# Board_Schamatic04.net
KiCad netlist of a schematic drawn in EAGLE
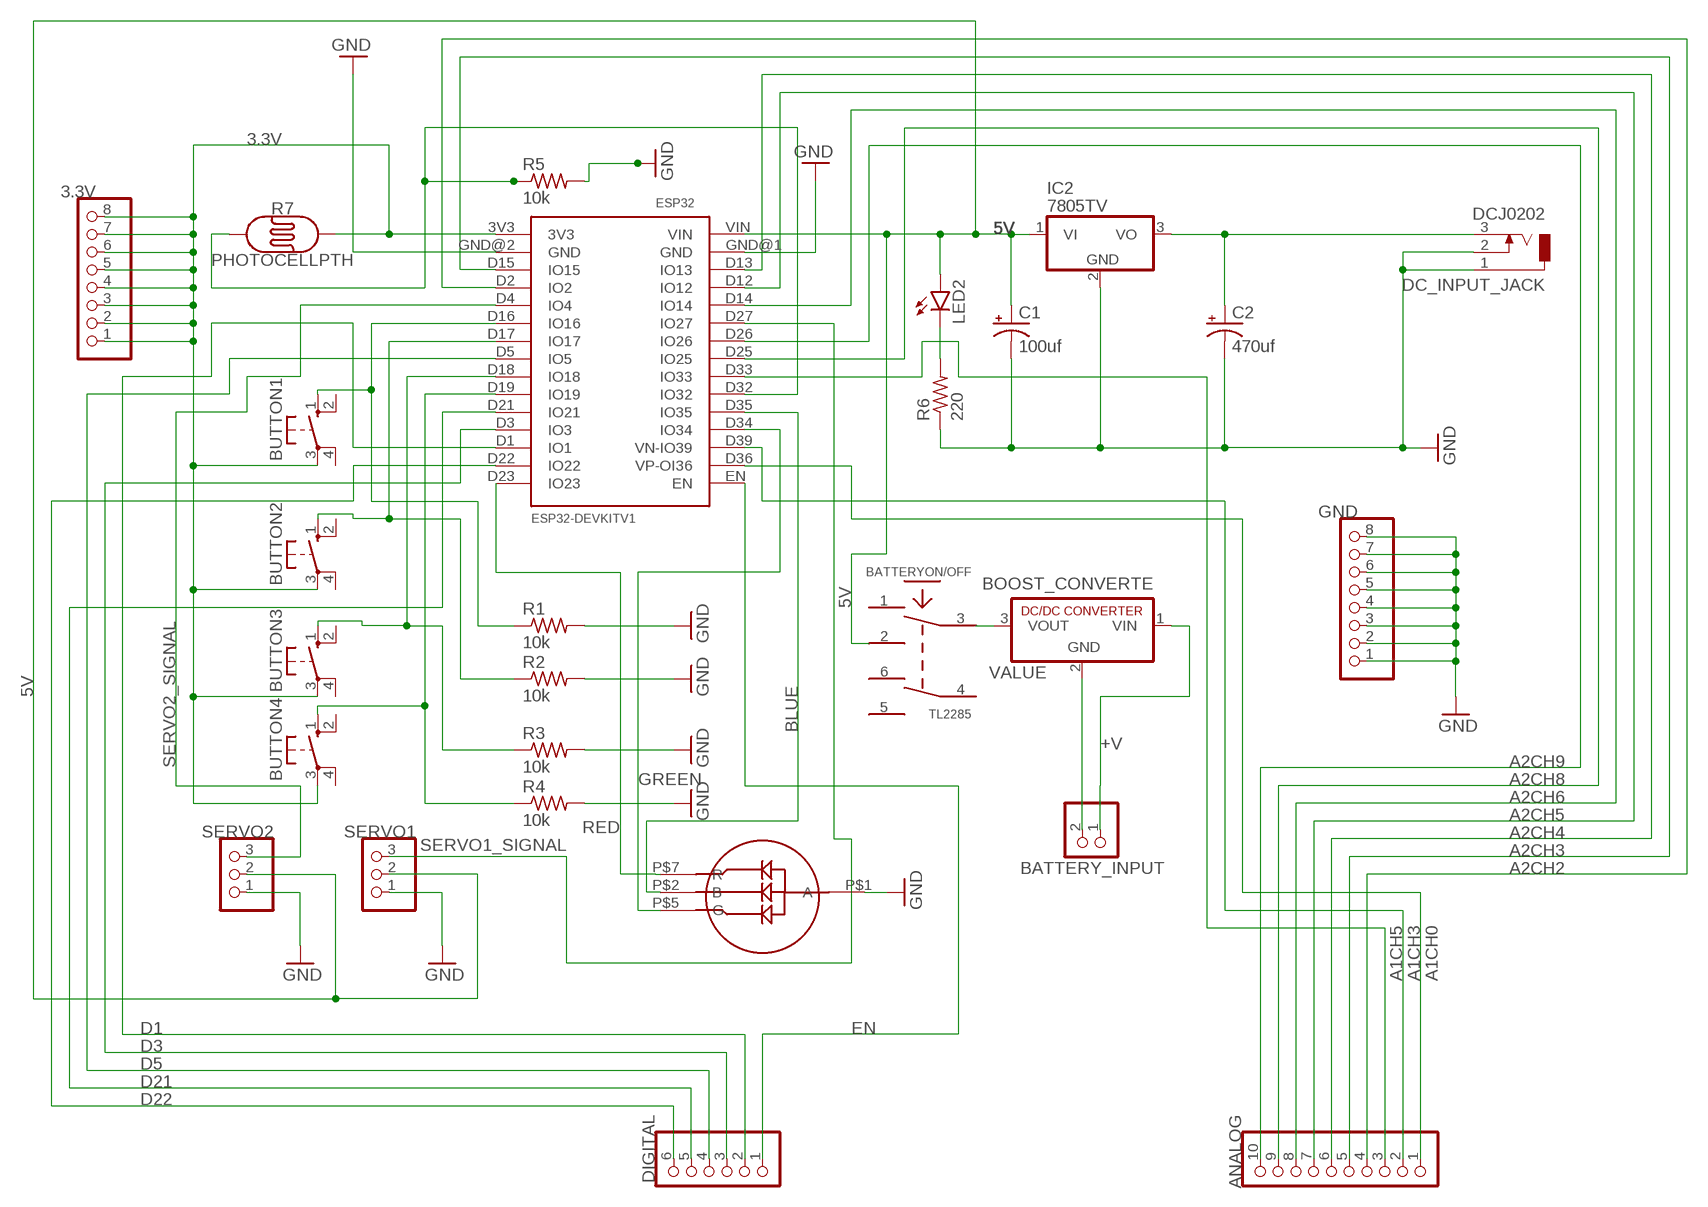
[diagram p0: schematic, sheet 1]

(export (version "E")
  (design (tool "Eeschema 10.0.6"))
  (components
    (comp (ref "3.3V")
      (value "PINHD-1X8")
      (footprint "eagle-import:1X08")
      (libsource (lib "eagle-import") (part "PINHD-1X8"))
    )
    (comp (ref "ANALOG")
      (value "PINHD-1X10")
      (footprint "eagle-import:1X10")
      (libsource (lib "eagle-import") (part "PINHD-1X10"))
    )
    (comp (ref "BATTERYON/OFF")
      (value "TL2285")
      (footprint "eagle-import:TL2285_PCB")
      (libsource (lib "eagle-import") (part "TL2285"))
    )
    (comp (ref "BATTERY_INPUT")
      (value "PINHD-1X2")
      (footprint "eagle-import:1X02")
      (libsource (lib "eagle-import") (part "PINHD-1X2"))
    )
    (comp (ref "BOOST_CONVERTE")
      (value "R-78C1.8-1.0")
      (footprint "eagle-import:SIP3")
      (libsource (lib "eagle-import") (part "R-78C-1.01.8"))
    )
    (comp (ref "BUTTON1")
      (value "10-XX")
      (footprint "eagle-import:B3F-10XX")
      (fields (field (name "MPN") "B3F-1000"))
      (libsource (lib "eagle-import") (part "10-XX"))
    )
    (comp (ref "BUTTON2")
      (value "10-XX")
      (footprint "eagle-import:B3F-10XX")
      (fields (field (name "MPN") "B3F-1000"))
      (libsource (lib "eagle-import") (part "10-XX"))
    )
    (comp (ref "BUTTON3")
      (value "10-XX")
      (footprint "eagle-import:B3F-10XX")
      (fields (field (name "MPN") "B3F-1000"))
      (libsource (lib "eagle-import") (part "10-XX"))
    )
    (comp (ref "BUTTON4")
      (value "10-XX")
      (footprint "eagle-import:B3F-10XX")
      (fields (field (name "MPN") "B3F-1000"))
      (libsource (lib "eagle-import") (part "10-XX"))
    )
    (comp (ref "C1")
      (value "100uf")
      (footprint "eagle-import:E2-5")
      (libsource (lib "eagle-import") (part "CPOL-USE2-5"))
    )
    (comp (ref "C2")
      (value "470uf")
      (footprint "eagle-import:E2-5")
      (libsource (lib "eagle-import") (part "CPOL-USE2-5"))
    )
    (comp (ref "DC_INPUT_JACK")
      (value "DCJ0202")
      (footprint "eagle-import:DCJ0202")
      (libsource (lib "eagle-import") (part "DCJ0202"))
    )
    (comp (ref "DIGITAL")
      (value "PINHD-1X6")
      (footprint "eagle-import:1X06")
      (libsource (lib "eagle-import") (part "PINHD-1X6"))
    )
    (comp (ref "ESP32")
      (value "ESP32DEVKITV1")
      (footprint "eagle-import:ESP32-DEVKITV1")
      (libsource (lib "eagle-import") (part "ESP32DEVKITV1"))
    )
    (comp (ref "GND")
      (value "PINHD-1X8")
      (footprint "eagle-import:1X08")
      (libsource (lib "eagle-import") (part "PINHD-1X8"))
    )
    (comp (ref "IC2")
      (value "7805TV")
      (footprint "eagle-import:TO220V")
      (libsource (lib "eagle-import") (part "78TV05"))
    )
    (comp (ref "LED-4_PIN1")
      (value "LED-4_PIN")
      (footprint "eagle-import:LED-4_PIN")
      (libsource (lib "eagle-import") (part "LED-4_PIN"))
    )
    (comp (ref "LED2")
      (value "LED5MM")
      (footprint "eagle-import:LED5MM")
      (libsource (lib "eagle-import") (part "LED5MM"))
    )
    (comp (ref "R1")
      (value "10k")
      (footprint "eagle-import:0207_10")
      (libsource (lib "eagle-import") (part "R-US_0207/10"))
    )
    (comp (ref "R2")
      (value "10k")
      (footprint "eagle-import:0207_10")
      (libsource (lib "eagle-import") (part "R-US_0207/10"))
    )
    (comp (ref "R3")
      (value "10k")
      (footprint "eagle-import:0207_10")
      (libsource (lib "eagle-import") (part "R-US_0207/10"))
    )
    (comp (ref "R4")
      (value "10k")
      (footprint "eagle-import:0207_10")
      (libsource (lib "eagle-import") (part "R-US_0207/10"))
    )
    (comp (ref "R5")
      (value "10k")
      (footprint "eagle-import:0207_10")
      (libsource (lib "eagle-import") (part "R-US_0207/10"))
    )
    (comp (ref "R6")
      (value "220")
      (footprint "eagle-import:0207_10")
      (libsource (lib "eagle-import") (part "R-US_0207/10"))
    )
    (comp (ref "R7")
      (value "PHOTOCELLPTH")
      (footprint "eagle-import:PHOTOCELL")
      (libsource (lib "eagle-import") (part "PHOTOCELLPTH"))
    )
    (comp (ref "SERVO1")
      (value "PINHD-1X3")
      (footprint "eagle-import:1X03")
      (libsource (lib "eagle-import") (part "PINHD-1X3"))
    )
    (comp (ref "SERVO2")
      (value "PINHD-1X3")
      (footprint "eagle-import:1X03")
      (libsource (lib "eagle-import") (part "PINHD-1X3"))
    )
  )
  (nets
    (net (code "1") (name "/+V") (class "Default")
      (node (ref "BATTERY_INPUT") (pin "1") (pinfunction "1_1") (pintype "passive"))
      (node (ref "BOOST_CONVERTE") (pin "1") (pinfunction "VIN_1") (pintype "passive"))
    )
    (net (code "2") (name "/3.3V") (class "Default")
      (node (ref "3.3V") (pin "1") (pinfunction "1_1") (pintype "passive"))
      (node (ref "3.3V") (pin "2") (pinfunction "2_2") (pintype "passive"))
      (node (ref "3.3V") (pin "3") (pinfunction "3_3") (pintype "passive"))
      (node (ref "3.3V") (pin "4") (pinfunction "4_4") (pintype "passive"))
      (node (ref "3.3V") (pin "5") (pinfunction "5_5") (pintype "passive"))
      (node (ref "3.3V") (pin "6") (pinfunction "6_6") (pintype "passive"))
      (node (ref "3.3V") (pin "7") (pinfunction "7_7") (pintype "passive"))
      (node (ref "3.3V") (pin "8") (pinfunction "8_8") (pintype "passive"))
      (node (ref "BUTTON1") (pin "3") (pinfunction "P_3") (pintype "passive"))
      (node (ref "BUTTON2") (pin "3") (pinfunction "P_3") (pintype "passive"))
      (node (ref "BUTTON3") (pin "3") (pinfunction "P_3") (pintype "passive"))
      (node (ref "BUTTON4") (pin "3") (pinfunction "P_3") (pintype "passive"))
      (node (ref "ESP32") (pin "3V3") (pinfunction "3V3_3V3") (pintype "bidirectional"))
      (node (ref "R7") (pin "2") (pinfunction "P$2_2") (pintype "bidirectional"))
    )
    (net (code "3") (name "/5V") (class "Default")
      (node (ref "BATTERYON/OFF") (pin "2") (pinfunction "P2_2") (pintype "bidirectional"))
      (node (ref "C1") (pin "+") (pinfunction "+_+") (pintype "passive"))
      (node (ref "ESP32") (pin "VIN") (pinfunction "VIN_VIN") (pintype "bidirectional"))
      (node (ref "IC2") (pin "1") (pinfunction "VI_1") (pintype "input"))
      (node (ref "LED2") (pin "A") (pinfunction "A_A") (pintype "passive"))
      (node (ref "SERVO1") (pin "2") (pinfunction "2_2") (pintype "passive"))
      (node (ref "SERVO2") (pin "2") (pinfunction "2_2") (pintype "passive"))
    )
    (net (code "4") (name "/A1CH0") (class "Default")
      (node (ref "ANALOG") (pin "1") (pinfunction "1_1") (pintype "passive"))
      (node (ref "ESP32") (pin "D36") (pinfunction "VP-OI36_D36") (pintype "bidirectional"))
    )
    (net (code "5") (name "/A1CH3") (class "Default")
      (node (ref "ANALOG") (pin "2") (pinfunction "2_2") (pintype "passive"))
      (node (ref "ESP32") (pin "D39") (pinfunction "VN-IO39_D39") (pintype "bidirectional"))
    )
    (net (code "6") (name "/A1CH5") (class "Default")
      (node (ref "ANALOG") (pin "3") (pinfunction "3_3") (pintype "passive"))
      (node (ref "ESP32") (pin "D33") (pinfunction "IO33_D33") (pintype "bidirectional"))
    )
    (net (code "7") (name "/A2CH2") (class "Default")
      (node (ref "ANALOG") (pin "4") (pinfunction "4_4") (pintype "passive"))
      (node (ref "ESP32") (pin "D2") (pinfunction "IO2_D2") (pintype "bidirectional"))
    )
    (net (code "8") (name "/A2CH3") (class "Default")
      (node (ref "ANALOG") (pin "5") (pinfunction "5_5") (pintype "passive"))
      (node (ref "ESP32") (pin "D15") (pinfunction "IO15_D15") (pintype "bidirectional"))
    )
    (net (code "9") (name "/A2CH4") (class "Default")
      (node (ref "ANALOG") (pin "6") (pinfunction "6_6") (pintype "passive"))
      (node (ref "ESP32") (pin "D13") (pinfunction "IO13_D13") (pintype "bidirectional"))
    )
    (net (code "10") (name "/A2CH5") (class "Default")
      (node (ref "ANALOG") (pin "7") (pinfunction "7_7") (pintype "passive"))
      (node (ref "ESP32") (pin "D12") (pinfunction "IO12_D12") (pintype "bidirectional"))
    )
    (net (code "11") (name "/A2CH6") (class "Default")
      (node (ref "ANALOG") (pin "8") (pinfunction "8_8") (pintype "passive"))
      (node (ref "ESP32") (pin "D14") (pinfunction "IO14_D14") (pintype "bidirectional"))
    )
    (net (code "12") (name "/A2CH8") (class "Default")
      (node (ref "ANALOG") (pin "9") (pinfunction "9_9") (pintype "passive"))
      (node (ref "ESP32") (pin "D25") (pinfunction "IO25_D25") (pintype "bidirectional"))
    )
    (net (code "13") (name "/A2CH9") (class "Default")
      (node (ref "ANALOG") (pin "10") (pinfunction "10_10") (pintype "passive"))
      (node (ref "ESP32") (pin "D26") (pinfunction "IO26_D26") (pintype "bidirectional"))
    )
    (net (code "14") (name "/BLUE") (class "Default")
      (node (ref "ESP32") (pin "D35") (pinfunction "IO35_D35") (pintype "bidirectional"))
      (node (ref "LED-4_PIN1") (pin "P$2") (pinfunction "B_P$2") (pintype "bidirectional"))
    )
    (net (code "15") (name "/D1") (class "Default")
      (node (ref "DIGITAL") (pin "2") (pinfunction "2_2") (pintype "passive"))
      (node (ref "ESP32") (pin "D1") (pinfunction "IO1_D1") (pintype "bidirectional"))
    )
    (net (code "16") (name "/D3") (class "Default")
      (node (ref "DIGITAL") (pin "3") (pinfunction "3_3") (pintype "passive"))
      (node (ref "ESP32") (pin "D3") (pinfunction "IO3_D3") (pintype "bidirectional"))
    )
    (net (code "17") (name "/D5") (class "Default")
      (node (ref "DIGITAL") (pin "4") (pinfunction "4_4") (pintype "passive"))
      (node (ref "ESP32") (pin "D5") (pinfunction "IO5_D5") (pintype "bidirectional"))
    )
    (net (code "18") (name "/D21") (class "Default")
      (node (ref "DIGITAL") (pin "5") (pinfunction "5_5") (pintype "passive"))
      (node (ref "ESP32") (pin "D21") (pinfunction "IO21_D21") (pintype "bidirectional"))
    )
    (net (code "19") (name "/D22") (class "Default")
      (node (ref "DIGITAL") (pin "6") (pinfunction "6_6") (pintype "passive"))
      (node (ref "ESP32") (pin "D22") (pinfunction "IO22_D22") (pintype "bidirectional"))
    )
    (net (code "20") (name "/EN") (class "Default")
      (node (ref "DIGITAL") (pin "1") (pinfunction "1_1") (pintype "passive"))
      (node (ref "ESP32") (pin "EN") (pinfunction "EN_EN") (pintype "bidirectional"))
    )
    (net (code "21") (name "/GREEN") (class "Default")
      (node (ref "ESP32") (pin "D34") (pinfunction "IO34_D34") (pintype "bidirectional"))
      (node (ref "LED-4_PIN1") (pin "P$5") (pinfunction "G_P$5") (pintype "bidirectional"))
    )
    (net (code "22") (name "/RED") (class "Default")
      (node (ref "ESP32") (pin "D23") (pinfunction "IO23_D23") (pintype "bidirectional"))
      (node (ref "LED-4_PIN1") (pin "P$7") (pinfunction "R_P$7") (pintype "bidirectional"))
    )
    (net (code "23") (name "/SERVO1_SIGNAL") (class "Default")
      (node (ref "ESP32") (pin "D27") (pinfunction "IO27_D27") (pintype "bidirectional"))
      (node (ref "SERVO1") (pin "3") (pinfunction "3_3") (pintype "passive"))
    )
    (net (code "24") (name "/SERVO2_SIGNAL") (class "Default")
      (node (ref "ESP32") (pin "D4") (pinfunction "IO4_D4") (pintype "bidirectional"))
      (node (ref "SERVO2") (pin "3") (pinfunction "3_3") (pintype "passive"))
    )
    (net (code "25") (name "GND") (class "Default")
      (node (ref "C1") (pin "-") (pinfunction "-_-") (pintype "passive"))
      (node (ref "C2") (pin "-") (pinfunction "-_-") (pintype "passive"))
      (node (ref "DC_INPUT_JACK") (pin "1") (pinfunction "1_1") (pintype "passive"))
      (node (ref "DC_INPUT_JACK") (pin "2") (pinfunction "2_2") (pintype "passive"))
      (node (ref "ESP32") (pin "GND@1") (pinfunction "GND_GND@1") (pintype "bidirectional"))
      (node (ref "ESP32") (pin "GND@2") (pinfunction "GND_GND@2") (pintype "bidirectional"))
      (node (ref "GND") (pin "1") (pinfunction "1_1") (pintype "passive"))
      (node (ref "GND") (pin "2") (pinfunction "2_2") (pintype "passive"))
      (node (ref "GND") (pin "3") (pinfunction "3_3") (pintype "passive"))
      (node (ref "GND") (pin "4") (pinfunction "4_4") (pintype "passive"))
      (node (ref "GND") (pin "5") (pinfunction "5_5") (pintype "passive"))
      (node (ref "GND") (pin "6") (pinfunction "6_6") (pintype "passive"))
      (node (ref "GND") (pin "7") (pinfunction "7_7") (pintype "passive"))
      (node (ref "GND") (pin "8") (pinfunction "8_8") (pintype "passive"))
      (node (ref "IC2") (pin "2") (pinfunction "GND_2") (pintype "passive"))
      (node (ref "LED-4_PIN1") (pin "P$1") (pinfunction "A_P$1") (pintype "bidirectional"))
      (node (ref "R1") (pin "2") (pinfunction "2_2") (pintype "passive"))
      (node (ref "R2") (pin "2") (pinfunction "2_2") (pintype "passive"))
      (node (ref "R3") (pin "2") (pinfunction "2_2") (pintype "passive"))
      (node (ref "R4") (pin "2") (pinfunction "2_2") (pintype "passive"))
      (node (ref "R5") (pin "2") (pinfunction "2_2") (pintype "passive"))
      (node (ref "R6") (pin "1") (pinfunction "1_1") (pintype "passive"))
      (node (ref "SERVO1") (pin "1") (pinfunction "1_1") (pintype "passive"))
      (node (ref "SERVO2") (pin "1") (pinfunction "1_1") (pintype "passive"))
    )
    (net (code "26") (name "Net-(BATTERYON/OFF-P3)") (class "Default")
      (node (ref "BATTERYON/OFF") (pin "3") (pinfunction "P3_3") (pintype "bidirectional"))
      (node (ref "BOOST_CONVERTE") (pin "3") (pinfunction "VOUT_3") (pintype "passive"))
    )
    (net (code "27") (name "Net-(BOOST_CONVERTE-GND)") (class "Default")
      (node (ref "BATTERY_INPUT") (pin "2") (pinfunction "2_2") (pintype "passive"))
      (node (ref "BOOST_CONVERTE") (pin "2") (pinfunction "GND_2") (pintype "passive"))
    )
    (net (code "28") (name "Net-(BUTTON1-S)") (class "Default")
      (node (ref "BUTTON1") (pin "1") (pinfunction "S_1") (pintype "passive"))
      (node (ref "ESP32") (pin "D16") (pinfunction "IO16_D16") (pintype "bidirectional"))
      (node (ref "R1") (pin "1") (pinfunction "1_1") (pintype "passive"))
    )
    (net (code "29") (name "Net-(BUTTON2-S)") (class "Default")
      (node (ref "BUTTON2") (pin "1") (pinfunction "S_1") (pintype "passive"))
      (node (ref "ESP32") (pin "D17") (pinfunction "IO17_D17") (pintype "bidirectional"))
      (node (ref "R2") (pin "1") (pinfunction "1_1") (pintype "passive"))
    )
    (net (code "30") (name "Net-(BUTTON3-S)") (class "Default")
      (node (ref "BUTTON3") (pin "1") (pinfunction "S_1") (pintype "passive"))
      (node (ref "ESP32") (pin "D18") (pinfunction "IO18_D18") (pintype "bidirectional"))
      (node (ref "R3") (pin "1") (pinfunction "1_1") (pintype "passive"))
    )
    (net (code "31") (name "Net-(BUTTON4-S)") (class "Default")
      (node (ref "BUTTON4") (pin "1") (pinfunction "S_1") (pintype "passive"))
      (node (ref "ESP32") (pin "D19") (pinfunction "IO19_D19") (pintype "bidirectional"))
      (node (ref "R4") (pin "1") (pinfunction "1_1") (pintype "passive"))
    )
    (net (code "32") (name "Net-(ESP32-IO32)") (class "Default")
      (node (ref "ESP32") (pin "D32") (pinfunction "IO32_D32") (pintype "bidirectional"))
      (node (ref "R5") (pin "1") (pinfunction "1_1") (pintype "passive"))
      (node (ref "R7") (pin "1") (pinfunction "P$1_1") (pintype "bidirectional"))
    )
    (net (code "33") (name "Net-(IC2-VO)") (class "Default")
      (node (ref "C2") (pin "+") (pinfunction "+_+") (pintype "passive"))
      (node (ref "DC_INPUT_JACK") (pin "3") (pinfunction "3_3") (pintype "passive"))
      (node (ref "IC2") (pin "3") (pinfunction "VO_3") (pintype "passive"))
    )
    (net (code "34") (name "Net-(LED2-C)") (class "Default")
      (node (ref "LED2") (pin "K") (pinfunction "C_K") (pintype "passive"))
      (node (ref "R6") (pin "2") (pinfunction "2_2") (pintype "passive"))
    )
    (net (code "35") (name "unconnected-(BATTERYON/OFF-P1-Pad1)") (class "Default")
      (node (ref "BATTERYON/OFF") (pin "1") (pinfunction "P1_1") (pintype "bidirectional"))
    )
    (net (code "36") (name "unconnected-(BATTERYON/OFF-P4-Pad4)") (class "Default")
      (node (ref "BATTERYON/OFF") (pin "4") (pinfunction "P4_4") (pintype "bidirectional"))
    )
    (net (code "37") (name "unconnected-(BATTERYON/OFF-P5-Pad5)") (class "Default")
      (node (ref "BATTERYON/OFF") (pin "5") (pinfunction "P5_5") (pintype "bidirectional"))
    )
    (net (code "38") (name "unconnected-(BATTERYON/OFF-P6-Pad6)") (class "Default")
      (node (ref "BATTERYON/OFF") (pin "6") (pinfunction "P6_6") (pintype "bidirectional"))
    )
    (net (code "39") (name "unconnected-(BUTTON1-P1-Pad4)") (class "Default")
      (node (ref "BUTTON1") (pin "4") (pinfunction "P1_4") (pintype "passive"))
    )
    (net (code "40") (name "unconnected-(BUTTON1-S1-Pad2)") (class "Default")
      (node (ref "BUTTON1") (pin "2") (pinfunction "S1_2") (pintype "passive"))
    )
    (net (code "41") (name "unconnected-(BUTTON2-P1-Pad4)") (class "Default")
      (node (ref "BUTTON2") (pin "4") (pinfunction "P1_4") (pintype "passive"))
    )
    (net (code "42") (name "unconnected-(BUTTON2-S1-Pad2)") (class "Default")
      (node (ref "BUTTON2") (pin "2") (pinfunction "S1_2") (pintype "passive"))
    )
    (net (code "43") (name "unconnected-(BUTTON3-P1-Pad4)") (class "Default")
      (node (ref "BUTTON3") (pin "4") (pinfunction "P1_4") (pintype "passive"))
    )
    (net (code "44") (name "unconnected-(BUTTON3-S1-Pad2)") (class "Default")
      (node (ref "BUTTON3") (pin "2") (pinfunction "S1_2") (pintype "passive"))
    )
    (net (code "45") (name "unconnected-(BUTTON4-P1-Pad4)") (class "Default")
      (node (ref "BUTTON4") (pin "4") (pinfunction "P1_4") (pintype "passive"))
    )
    (net (code "46") (name "unconnected-(BUTTON4-S1-Pad2)") (class "Default")
      (node (ref "BUTTON4") (pin "2") (pinfunction "S1_2") (pintype "passive"))
    )
  )
)
